# Communication.net
KiCad netlist of a schematic drawn in Altium Designer
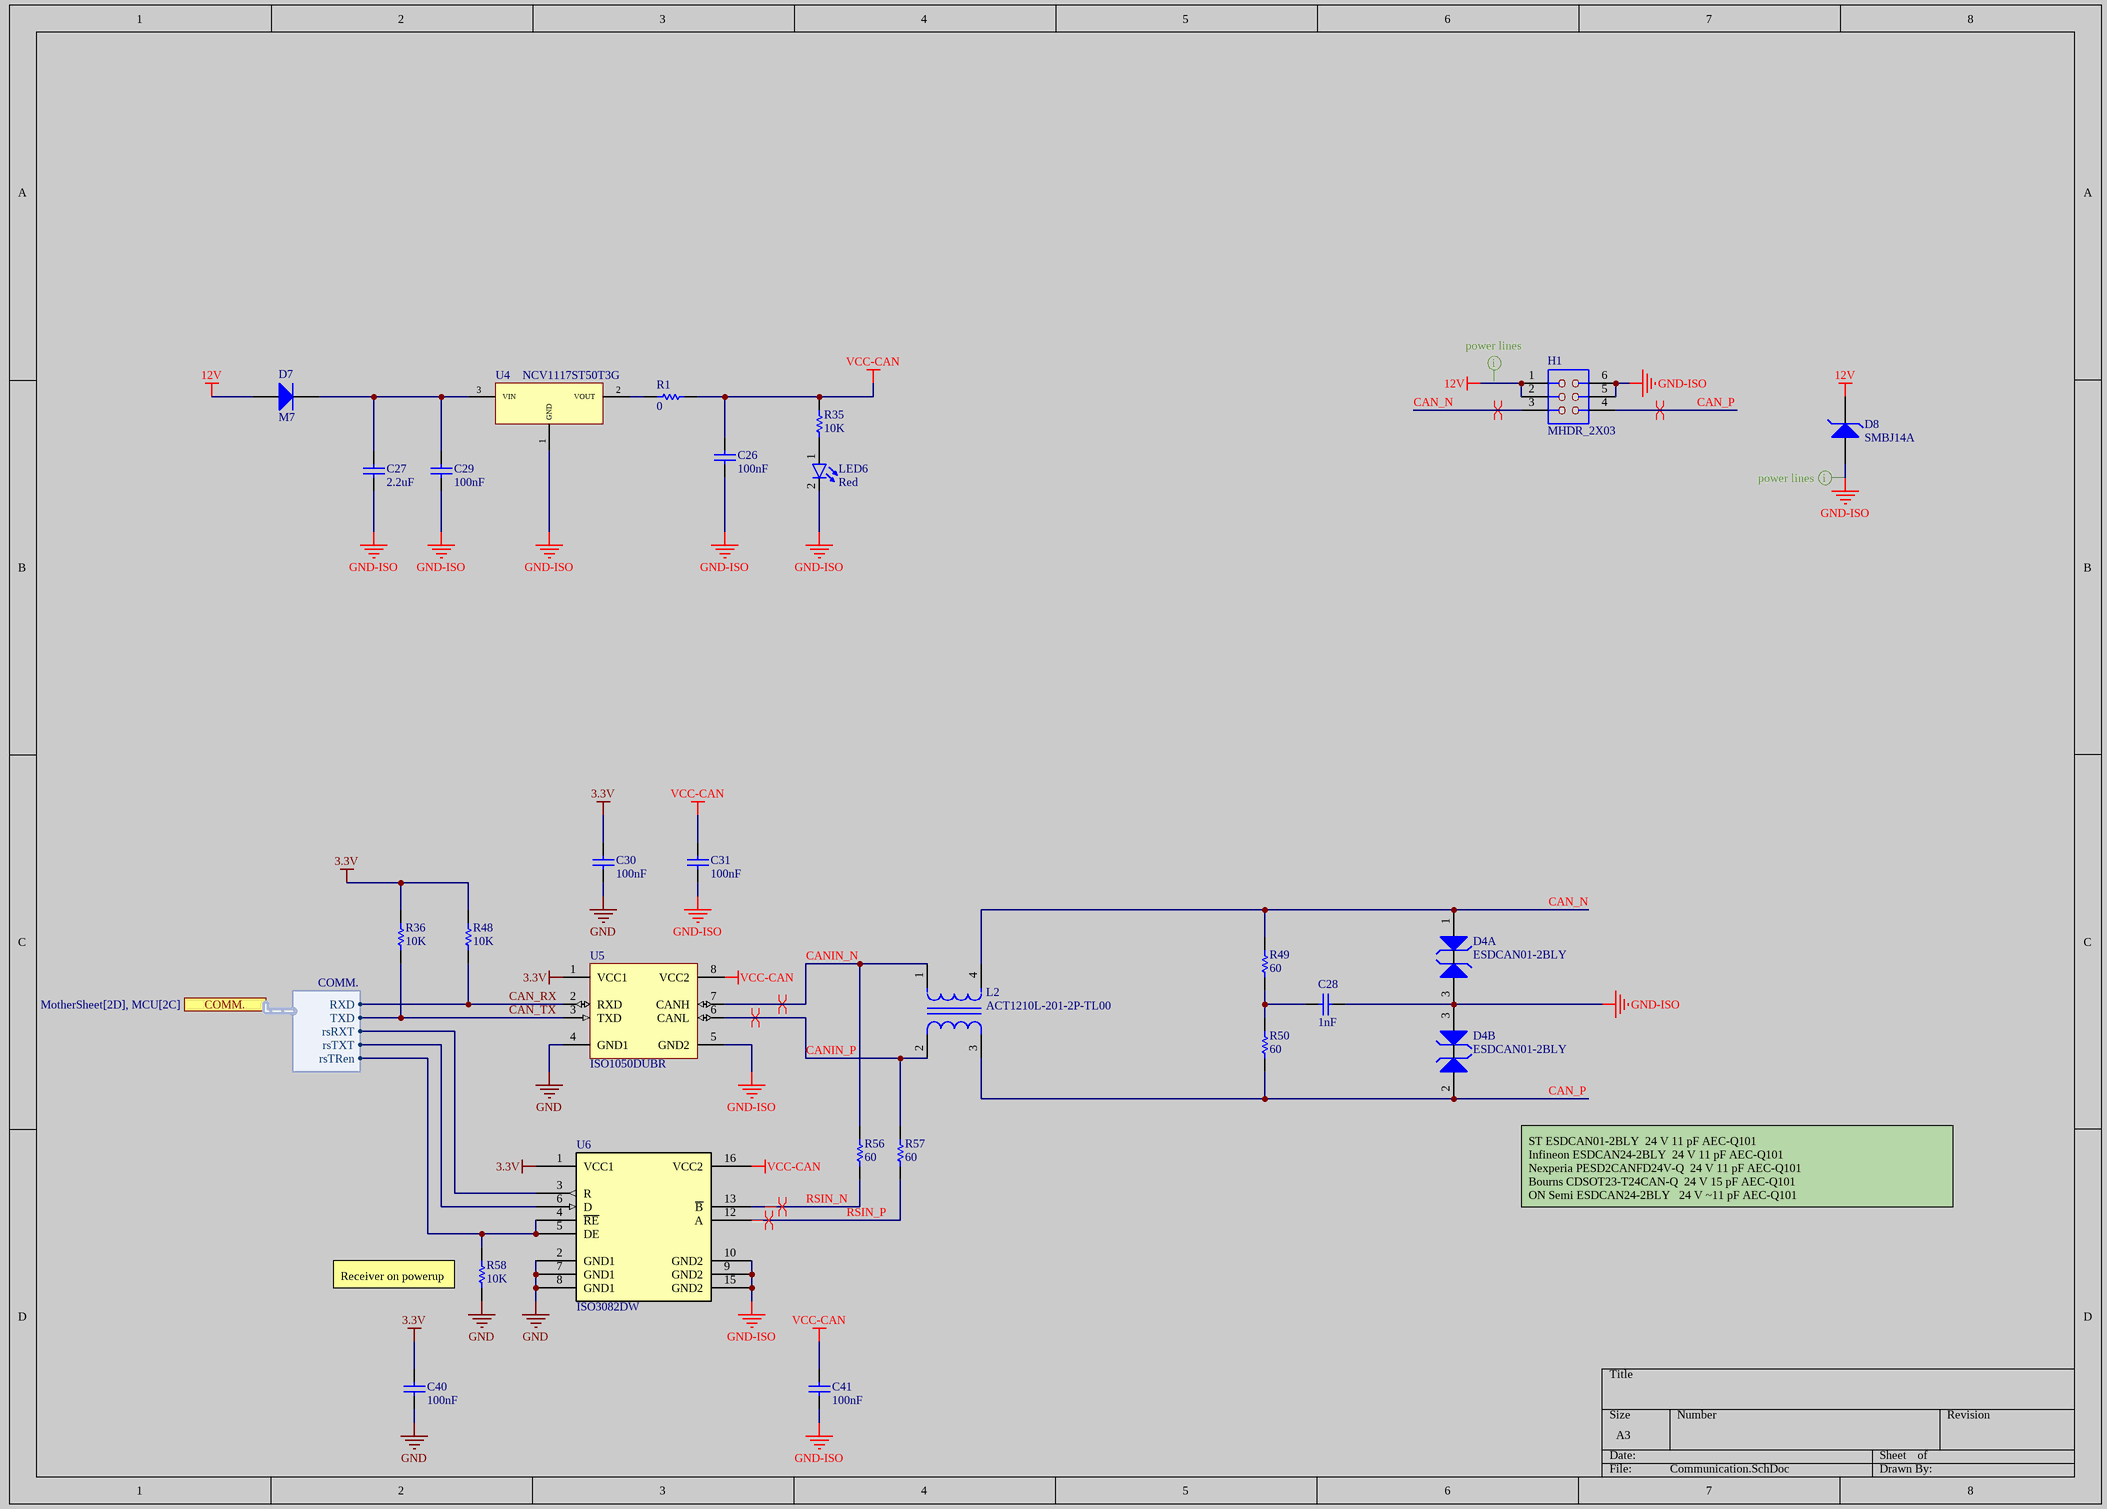
[diagram p0: Communication.SchDoc]

(export (version "E")
  (design (tool "Eeschema 10.0.6"))
  (components
    (comp (ref "C26")
      (value "100nF")
      (footprint "CAPC0603")
      (description "Capacitor")
      (fields (field (name "PUBLISHER") "Altium Limited"))
      (libsource (lib "eLIB") (part "Capacitor"))
    )
    (comp (ref "C27")
      (value "2.2uF")
      (footprint "cap1206")
      (description "Capacitor")
      (fields (field (name "PUBLISHER") "Altium Limited"))
      (libsource (lib "eLIB") (part "Capacitor"))
    )
    (comp (ref "C28")
      (value "1nF")
      (footprint "CAP0603")
      (description "Capacitor")
      (fields (field (name "PUBLISHER") "Altium Limited"))
      (libsource (lib "MyLibrary") (part "Capacitor"))
    )
    (comp (ref "C29")
      (value "100nF")
      (footprint "CAPC0603")
      (description "Capacitor")
      (fields (field (name "PUBLISHER") "Altium Limited"))
      (libsource (lib "eLIB") (part "Capacitor"))
    )
    (comp (ref "C30")
      (value "100nF")
      (footprint "CAPC0603")
      (description "Capacitor")
      (fields (field (name "PUBLISHER") "Altium Limited"))
      (libsource (lib "eLIB") (part "Capacitor"))
    )
    (comp (ref "C31")
      (value "100nF")
      (footprint "CAPC0603")
      (description "Capacitor")
      (fields (field (name "PUBLISHER") "Altium Limited"))
      (libsource (lib "eLIB") (part "Capacitor"))
    )
    (comp (ref "C40")
      (value "100nF")
      (footprint "CAPC0603")
      (description "Capacitor")
      (fields (field (name "PUBLISHER") "Altium Limited"))
      (libsource (lib "eLIB") (part "Capacitor"))
    )
    (comp (ref "C41")
      (value "100nF")
      (footprint "CAPC0603")
      (description "Capacitor")
      (fields (field (name "PUBLISHER") "Altium Limited"))
      (libsource (lib "eLIB") (part "Capacitor"))
    )
    (comp (ref "D4")
      (value "ESDCAN01-2BLY")
      (footprint "NPN")
      (description "transiebt voltage suppressor")
      (libsource (lib "eLIB") (part "TVS"))
    )
    (comp (ref "D7") (value "M7") (footprint "SS36") (libsource (lib "SINA") (part "SS36")))
    (comp (ref "D8")
      (value "SMBJ14A")
      (footprint "SMBJSeries_LTF-M")
      (description "ESD protection diode / TVS diodes")
      (libsource (lib "SINA") (part "SMBJ14ALK"))
    )
    (comp (ref "H1")
      (value "MHDR_2X03")
      (footprint "miniATX 2 × 3")
      (description "Male Header 2X03")
      (libsource (lib "eLIB") (part "HDR_mini_2 × 3"))
    )
    (comp (ref "L2")
      (value "ACT1210L-201-2P-TL00")
      (footprint "FP-ACT1210L-MFG")
      (description "CMC 200UH 70MA 2LN SMD")
      (fields
        (field (name "MANUFACTURER") "TDK")
        (field (name "OCTOPART") "https://octopart.com/act1210l-201-2p-tl00-tdk-81014617")
      )
      (libsource (lib "eLIB") (part "line filter CMP-08256-000003-1"))
    )
    (comp (ref "LED6")
      (value "Red")
      (footprint "led")
      (description "LED")
      (fields (field (name "COLOR") "Red") (field (name "DESIGNER") "Saeid Jorablo"))
      (libsource (lib "TaraSchlib") (part "LED"))
    )
    (comp (ref "R1")
      (value "0")
      (footprint "RES0603")
      (description "Resistor")
      (fields (field (name "PUBLISHER") "Altium Limited"))
      (libsource (lib "TaraSchlib") (part "Res"))
    )
    (comp (ref "R35")
      (value "10K")
      (footprint "RES0603")
      (description "Resistor")
      (fields (field (name "PUBLISHER") "Altium Limited"))
      (libsource (lib "TaraSchlib") (part "Res"))
    )
    (comp (ref "R36")
      (value "10K")
      (footprint "RES0603")
      (description "Resistor")
      (fields (field (name "PUBLISHER") "Altium Limited"))
      (libsource (lib "TaraSchlib") (part "Res"))
    )
    (comp (ref "R48")
      (value "10K")
      (footprint "RES0603")
      (description "Resistor")
      (fields (field (name "PUBLISHER") "Altium Limited"))
      (libsource (lib "TaraSchlib") (part "Res"))
    )
    (comp (ref "R49")
      (value "60")
      (footprint "RES0603")
      (description "Resistor")
      (fields (field (name "PUBLISHER") "Altium Limited"))
      (libsource (lib "TaraSchlib") (part "Res"))
    )
    (comp (ref "R50")
      (value "60")
      (footprint "RES0603")
      (description "Resistor")
      (fields (field (name "PUBLISHER") "Altium Limited"))
      (libsource (lib "TaraSchlib") (part "Res"))
    )
    (comp (ref "R56")
      (value "60")
      (footprint "RES0603")
      (description "Resistor")
      (fields (field (name "PUBLISHER") "Altium Limited"))
      (libsource (lib "TaraSchlib") (part "Res"))
    )
    (comp (ref "R57")
      (value "60")
      (footprint "RES0603")
      (description "Resistor")
      (fields (field (name "PUBLISHER") "Altium Limited"))
      (libsource (lib "TaraSchlib") (part "Res"))
    )
    (comp (ref "R58")
      (value "10K")
      (footprint "RES0603")
      (description "Resistor")
      (fields (field (name "PUBLISHER") "Altium Limited"))
      (libsource (lib "TaraSchlib") (part "Res"))
    )
    (comp (ref "U4")
      (value "NCV1117ST50T3G")
      (footprint "AMS1117")
      (description "NCP1117ST50T3G LDO 5V")
      (libsource (lib "eLIB") (part "AMS1117"))
    )
    (comp (ref "U5")
      (value "ISO1050DUBR")
      (footprint "soic 8")
      (description "Isolated CAN Transceiver, -55 to 105 degC, 8-pin SOP (DUB), Green (RoHS & no Sb/Br)")
      (fields (field (name "MANUFACTURER") "Texas Instruments"))
      (libsource (lib "eLIB") (part "ISO1050DUBR"))
    )
    (comp (ref "U6")
      (value "ISO3082DW")
      (footprint "DW16")
      (description "200-Kbps, half-duplex, 2.5-kVrms isolated RS-485 & RS-422 transceiver 16-SOIC -40 to 85")
      (fields (field (name "COPYRIGHT") "Copyright (C) 2025 Ultra Librarian. All rights reserved."))
      (libsource (lib "SINA") (part "ISO3082DW"))
    )
  )
  (nets
    (net (code "2") (name "/CANIN_N") (class "Default")
      (node (ref "L2") (pin "1") (pinfunction "1_1") (pintype "passive"))
      (node (ref "R56") (pin "2") (pinfunction "2_2") (pintype "passive"))
      (node (ref "U5") (pin "7") (pinfunction "CANH_7") (pintype "bidirectional"))
    )
    (net (code "3") (name "/CANIN_P") (class "Default")
      (node (ref "L2") (pin "2") (pinfunction "2_2") (pintype "passive"))
      (node (ref "R57") (pin "1") (pinfunction "1_1") (pintype "passive"))
      (node (ref "U5") (pin "6") (pinfunction "CANL_6") (pintype "bidirectional"))
    )
    (net (code "4") (name "/CAN_N") (class "Default")
      (node (ref "D4") (pin "1") (pinfunction "A_1") (pintype "passive"))
      (node (ref "H1") (pin "3") (pinfunction "3_3") (pintype "passive"))
      (node (ref "L2") (pin "4") (pinfunction "4_4") (pintype "passive"))
      (node (ref "R49") (pin "1") (pinfunction "1_1") (pintype "passive"))
    )
    (net (code "5") (name "/CAN_P") (class "Default")
      (node (ref "D4") (pin "2") (pinfunction "A_2") (pintype "passive"))
      (node (ref "H1") (pin "4") (pinfunction "4_4") (pintype "passive"))
      (node (ref "L2") (pin "3") (pinfunction "3_3") (pintype "passive"))
      (node (ref "R50") (pin "1") (pinfunction "1_1") (pintype "passive"))
    )
    (net (code "6") (name "/CAN_RX") (class "Default")
      (node (ref "R48") (pin "2") (pinfunction "2_2") (pintype "passive"))
      (node (ref "U5") (pin "2") (pinfunction "RXD_2") (pintype "bidirectional"))
    )
    (net (code "7") (name "/CAN_TX") (class "Default")
      (node (ref "R36") (pin "2") (pinfunction "2_2") (pintype "passive"))
      (node (ref "U5") (pin "3") (pinfunction "TXD_3") (pintype "input"))
    )
    (net (code "8") (name "/RSIN_N") (class "Default")
      (node (ref "R56") (pin "1") (pinfunction "1_1") (pintype "passive"))
      (node (ref "U6") (pin "13") (pinfunction "~{B}_13") (pintype "passive"))
    )
    (net (code "9") (name "/RSIN_P") (class "Default")
      (node (ref "R57") (pin "2") (pinfunction "2_2") (pintype "passive"))
      (node (ref "U6") (pin "12") (pinfunction "A_12") (pintype "passive"))
    )
    (net (code "10") (name "/rsRXT") (class "Default")
      (node (ref "U6") (pin "3") (pinfunction "R_3") (pintype "output"))
    )
    (net (code "11") (name "/rsTRen") (class "Default")
      (node (ref "R58") (pin "1") (pinfunction "1_1") (pintype "passive"))
      (node (ref "U6") (pin "4") (pinfunction "~{RE}_4") (pintype "passive"))
      (node (ref "U6") (pin "5") (pinfunction "DE_5") (pintype "passive"))
    )
    (net (code "12") (name "/rsTXT") (class "Default")
      (node (ref "U6") (pin "6") (pinfunction "D_6") (pintype "input"))
    )
    (net (code "14") (name "3.3V") (class "Default")
      (node (ref "C30") (pin "2") (pinfunction "2_2") (pintype "passive"))
      (node (ref "C40") (pin "2") (pinfunction "2_2") (pintype "passive"))
      (node (ref "R36") (pin "1") (pinfunction "1_1") (pintype "passive"))
      (node (ref "R48") (pin "1") (pinfunction "1_1") (pintype "passive"))
      (node (ref "U5") (pin "1") (pinfunction "VCC1_1") (pintype "power_in"))
      (node (ref "U6") (pin "1") (pinfunction "VCC1_1") (pintype "power_in"))
    )
    (net (code "15") (name "12V") (class "Default")
      (node (ref "D7") (pin "1") (pinfunction "A_1") (pintype "passive"))
      (node (ref "D8") (pin "1") (pinfunction "A_1") (pintype "passive"))
      (node (ref "H1") (pin "1") (pinfunction "1_1") (pintype "passive"))
      (node (ref "H1") (pin "2") (pinfunction "2_2") (pintype "passive"))
    )
    (net (code "16") (name "GND") (class "Default")
      (node (ref "C30") (pin "1") (pinfunction "1_1") (pintype "passive"))
      (node (ref "C40") (pin "1") (pinfunction "1_1") (pintype "passive"))
      (node (ref "R58") (pin "2") (pinfunction "2_2") (pintype "passive"))
      (node (ref "U5") (pin "4") (pinfunction "GND1_4") (pintype "power_in"))
      (node (ref "U6") (pin "2") (pinfunction "GND1_2") (pintype "power_in"))
      (node (ref "U6") (pin "7") (pinfunction "GND1_7") (pintype "power_in"))
      (node (ref "U6") (pin "8") (pinfunction "GND1_8") (pintype "power_in"))
    )
    (net (code "17") (name "GND-ISO") (class "Default")
      (node (ref "C26") (pin "1") (pinfunction "1_1") (pintype "passive"))
      (node (ref "C27") (pin "1") (pinfunction "1_1") (pintype "passive"))
      (node (ref "C28") (pin "1") (pinfunction "1_1") (pintype "passive"))
      (node (ref "C29") (pin "1") (pinfunction "1_1") (pintype "passive"))
      (node (ref "C31") (pin "1") (pinfunction "1_1") (pintype "passive"))
      (node (ref "C41") (pin "1") (pinfunction "1_1") (pintype "passive"))
      (node (ref "D4") (pin "3") (pinfunction "C_3") (pintype "passive"))
      (node (ref "D8") (pin "2") (pinfunction "B_2") (pintype "passive"))
      (node (ref "H1") (pin "5") (pinfunction "5_5") (pintype "passive"))
      (node (ref "H1") (pin "6") (pinfunction "6_6") (pintype "passive"))
      (node (ref "LED6") (pin "2") (pinfunction "K_2") (pintype "passive"))
      (node (ref "U4") (pin "1") (pinfunction "GND_1") (pintype "passive"))
      (node (ref "U5") (pin "5") (pinfunction "GND2_5") (pintype "power_in"))
      (node (ref "U6") (pin "10") (pinfunction "GND2_10") (pintype "power_in"))
      (node (ref "U6") (pin "15") (pinfunction "GND2_15") (pintype "power_in"))
      (node (ref "U6") (pin "9") (pinfunction "GND2_9") (pintype "power_in"))
    )
    (net (code "18") (name "Net-(C28-Pad2)") (class "Default")
      (node (ref "C28") (pin "2") (pinfunction "2_2") (pintype "passive"))
      (node (ref "R49") (pin "2") (pinfunction "2_2") (pintype "passive"))
      (node (ref "R50") (pin "2") (pinfunction "2_2") (pintype "passive"))
    )
    (net (code "19") (name "Net-(D7-K)") (class "Default")
      (node (ref "C27") (pin "2") (pinfunction "2_2") (pintype "passive"))
      (node (ref "C29") (pin "2") (pinfunction "2_2") (pintype "passive"))
      (node (ref "D7") (pin "2") (pinfunction "K_2") (pintype "passive"))
      (node (ref "U4") (pin "3") (pinfunction "VIN_3") (pintype "passive"))
    )
    (net (code "20") (name "Net-(LED6-A)") (class "Default")
      (node (ref "LED6") (pin "1") (pinfunction "A_1") (pintype "passive"))
      (node (ref "R35") (pin "2") (pinfunction "2_2") (pintype "passive"))
    )
    (net (code "21") (name "Net-(U4-VOUT)") (class "Default")
      (node (ref "R1") (pin "1") (pinfunction "1_1") (pintype "passive"))
      (node (ref "U4") (pin "2") (pinfunction "VOUT_2") (pintype "passive"))
    )
    (net (code "22") (name "VCC-CAN") (class "Default")
      (node (ref "C26") (pin "2") (pinfunction "2_2") (pintype "passive"))
      (node (ref "C31") (pin "2") (pinfunction "2_2") (pintype "passive"))
      (node (ref "C41") (pin "2") (pinfunction "2_2") (pintype "passive"))
      (node (ref "R1") (pin "2") (pinfunction "2_2") (pintype "passive"))
      (node (ref "R35") (pin "1") (pinfunction "1_1") (pintype "passive"))
      (node (ref "U5") (pin "8") (pinfunction "VCC2_8") (pintype "power_in"))
      (node (ref "U6") (pin "16") (pinfunction "VCC2_16") (pintype "power_in"))
    )
  )
)
